# keyboard.net
KiCad netlist of a schematic drawn in EAGLE
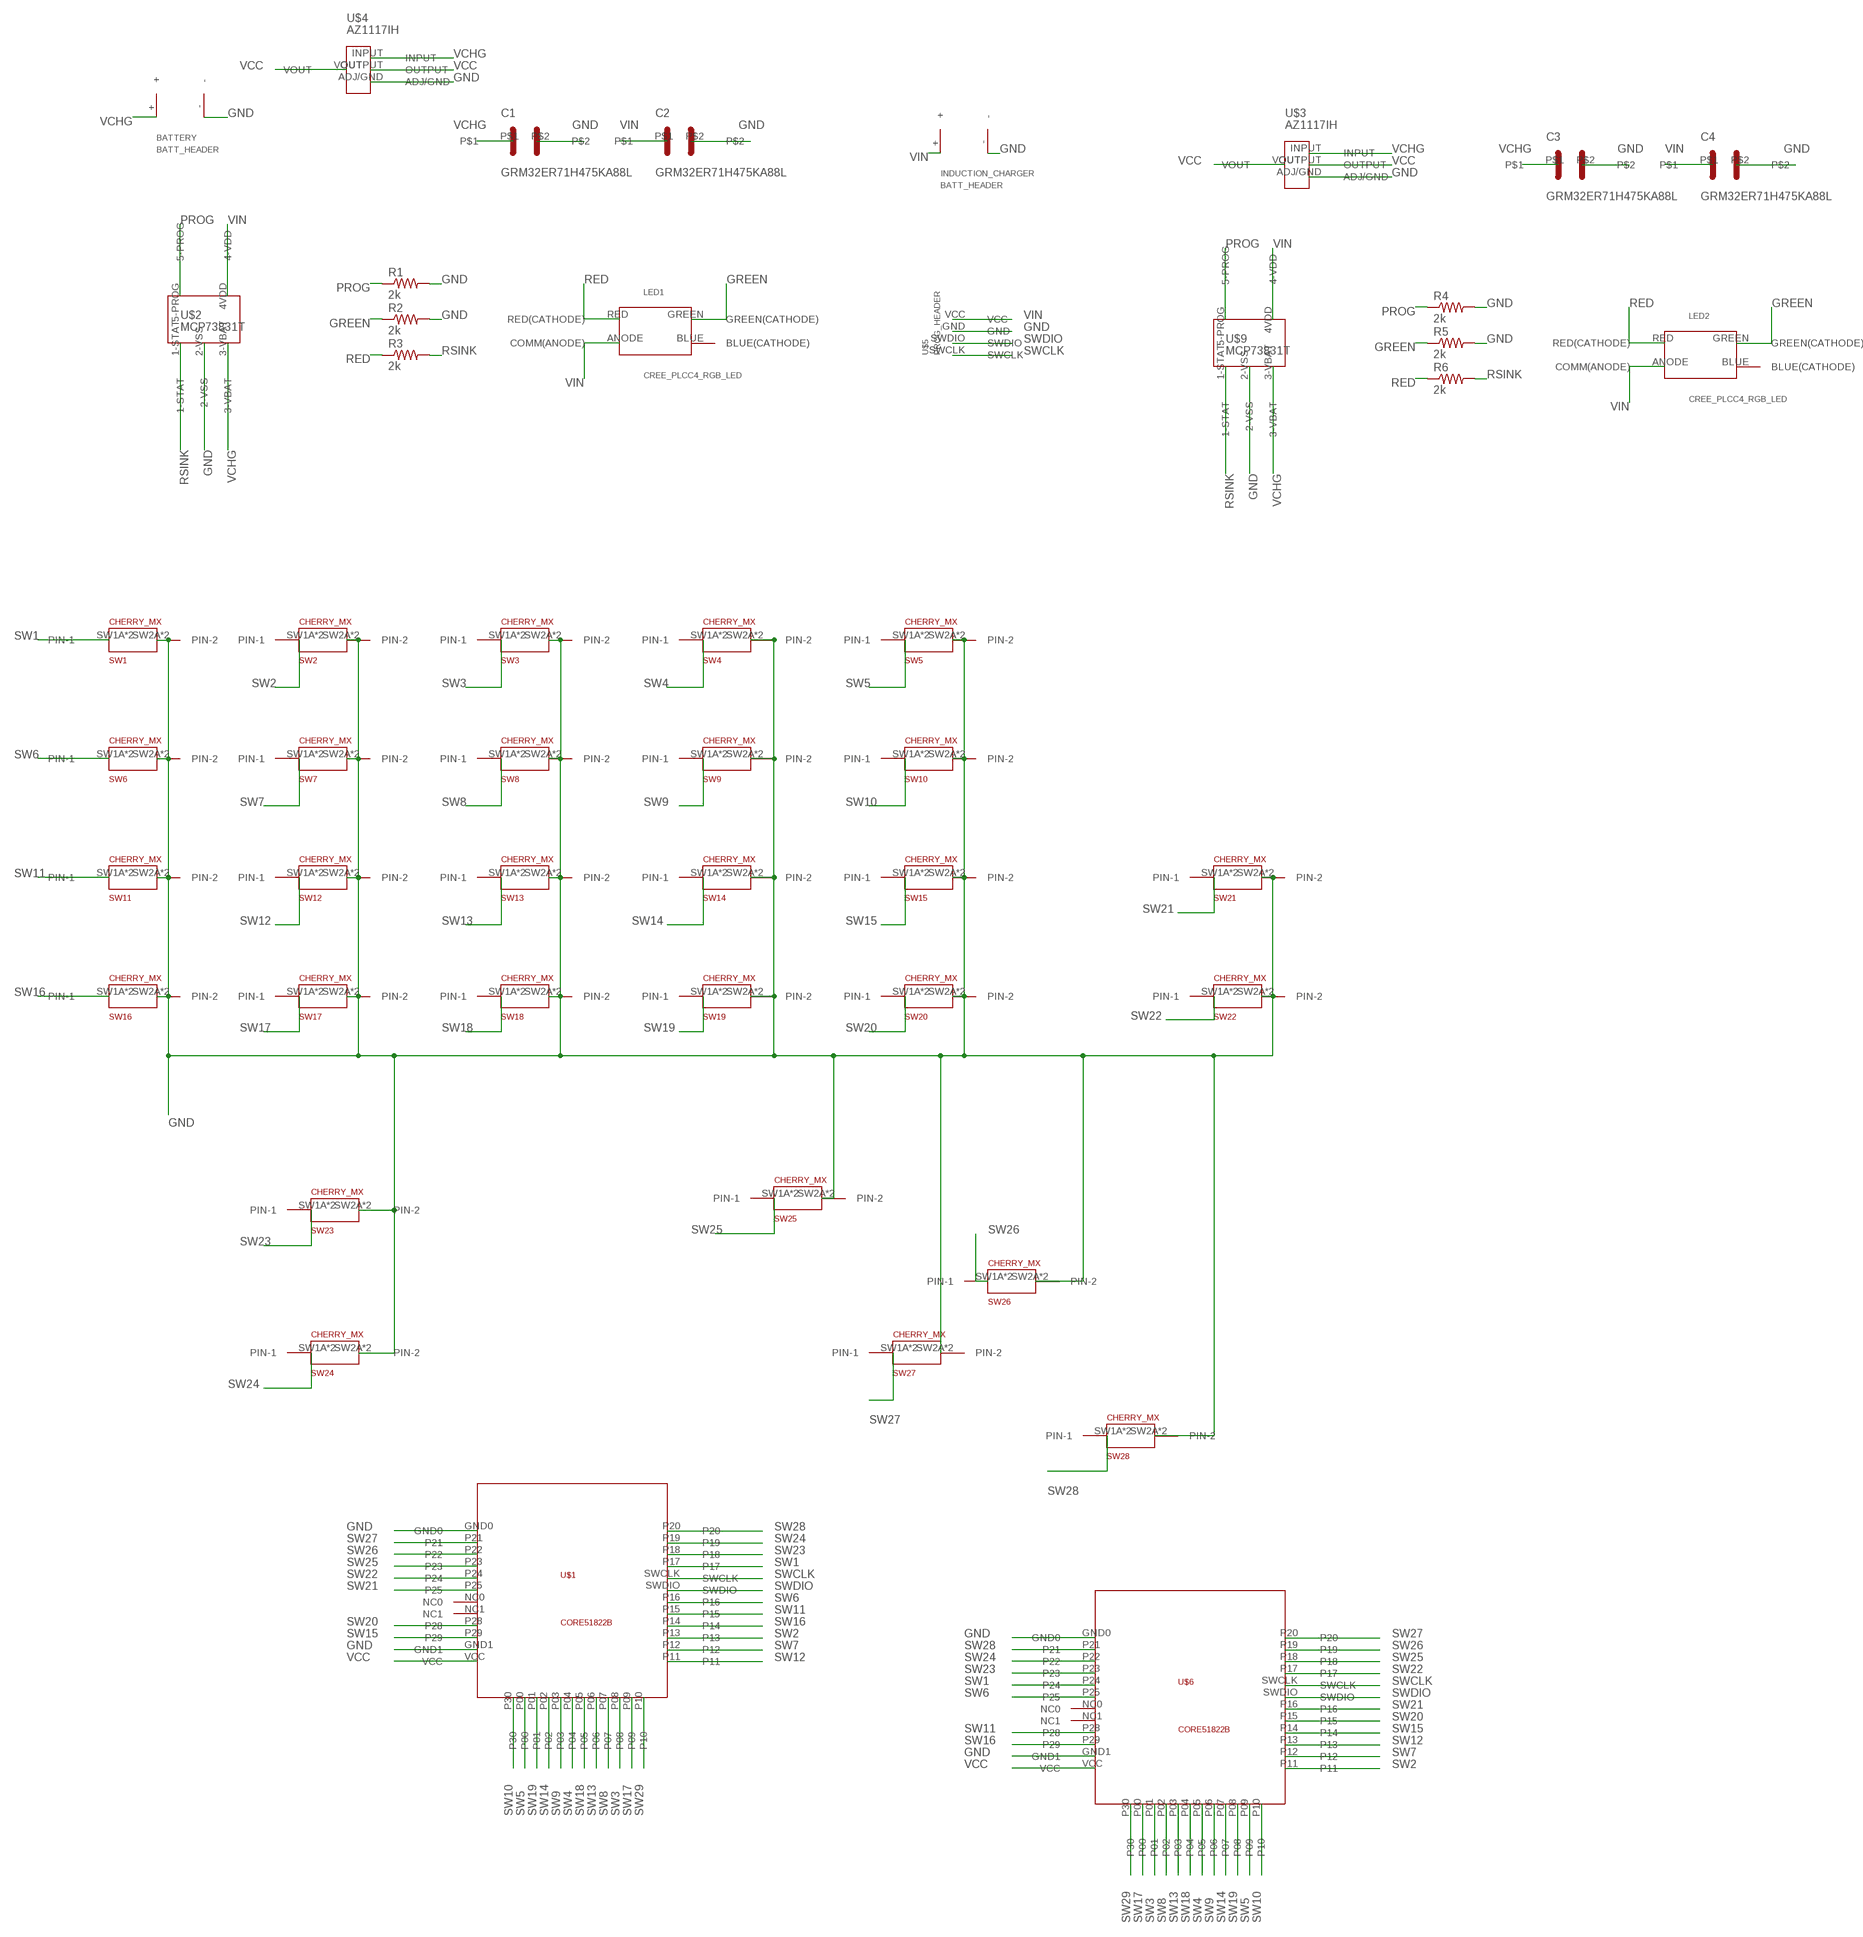
[diagram p0: schematic, sheet 1]

(export (version "E")
  (design (tool "Eeschema 10.0.6"))
  (components
    (comp (ref "BATTERY")
      (value "BATT_HEADER")
      (footprint "eagle-import:BATT_HEADER")
      (libsource (lib "eagle-import") (part "BATT_HEADER"))
    )
    (comp (ref "C1")
      (value "GRM32ER71H475KA88L")
      (footprint "eagle-import:GRM32ER71H475KA88L")
      (libsource (lib "eagle-import") (part "GRM32ER71H475KA88L"))
    )
    (comp (ref "C2")
      (value "GRM32ER71H475KA88L")
      (footprint "eagle-import:GRM32ER71H475KA88L")
      (libsource (lib "eagle-import") (part "GRM32ER71H475KA88L"))
    )
    (comp (ref "C3")
      (value "GRM32ER71H475KA88L")
      (footprint "eagle-import:GRM32ER71H475KA88L")
      (libsource (lib "eagle-import") (part "GRM32ER71H475KA88L"))
    )
    (comp (ref "C4")
      (value "GRM32ER71H475KA88L")
      (footprint "eagle-import:GRM32ER71H475KA88L")
      (libsource (lib "eagle-import") (part "GRM32ER71H475KA88L"))
    )
    (comp (ref "INDUCTION_CHARGER")
      (value "BATT_HEADER")
      (footprint "eagle-import:BATT_HEADER")
      (libsource (lib "eagle-import") (part "BATT_HEADER"))
    )
    (comp (ref "LED1")
      (value "CREE_PLCC4_RGB_LED")
      (footprint "eagle-import:4-PLCC")
      (libsource (lib "eagle-import") (part "CREE_PLCC4_RGB_LED"))
    )
    (comp (ref "LED2")
      (value "CREE_PLCC4_RGB_LED")
      (footprint "eagle-import:4-PLCC")
      (libsource (lib "eagle-import") (part "CREE_PLCC4_RGB_LED"))
    )
    (comp (ref "R1")
      (value "2k")
      (footprint "eagle-import:R1210")
      (libsource (lib "eagle-import") (part "R-US_R1210"))
    )
    (comp (ref "R2")
      (value "2k")
      (footprint "eagle-import:R1210")
      (libsource (lib "eagle-import") (part "R-US_R1210"))
    )
    (comp (ref "R3")
      (value "2k")
      (footprint "eagle-import:R1210")
      (libsource (lib "eagle-import") (part "R-US_R1210"))
    )
    (comp (ref "R4")
      (value "2k")
      (footprint "eagle-import:R1210")
      (libsource (lib "eagle-import") (part "R-US_R1210"))
    )
    (comp (ref "R5")
      (value "2k")
      (footprint "eagle-import:R1210")
      (libsource (lib "eagle-import") (part "R-US_R1210"))
    )
    (comp (ref "R6")
      (value "2k")
      (footprint "eagle-import:R1210")
      (libsource (lib "eagle-import") (part "R-US_R1210"))
    )
    (comp (ref "SW1")
      (value "CHERRY_MX")
      (footprint "eagle-import:CHERRY_MX")
      (libsource (lib "eagle-import") (part "CHERRY_MX"))
    )
    (comp (ref "SW2")
      (value "CHERRY_MX")
      (footprint "eagle-import:CHERRY_MX")
      (libsource (lib "eagle-import") (part "CHERRY_MX"))
    )
    (comp (ref "SW3")
      (value "CHERRY_MX")
      (footprint "eagle-import:CHERRY_MX")
      (libsource (lib "eagle-import") (part "CHERRY_MX"))
    )
    (comp (ref "SW4")
      (value "CHERRY_MX")
      (footprint "eagle-import:CHERRY_MX")
      (libsource (lib "eagle-import") (part "CHERRY_MX"))
    )
    (comp (ref "SW5")
      (value "CHERRY_MX")
      (footprint "eagle-import:CHERRY_MX")
      (libsource (lib "eagle-import") (part "CHERRY_MX"))
    )
    (comp (ref "SW6")
      (value "CHERRY_MX")
      (footprint "eagle-import:CHERRY_MX")
      (libsource (lib "eagle-import") (part "CHERRY_MX"))
    )
    (comp (ref "SW7")
      (value "CHERRY_MX")
      (footprint "eagle-import:CHERRY_MX")
      (libsource (lib "eagle-import") (part "CHERRY_MX"))
    )
    (comp (ref "SW8")
      (value "CHERRY_MX")
      (footprint "eagle-import:CHERRY_MX")
      (libsource (lib "eagle-import") (part "CHERRY_MX"))
    )
    (comp (ref "SW9")
      (value "CHERRY_MX")
      (footprint "eagle-import:CHERRY_MX")
      (libsource (lib "eagle-import") (part "CHERRY_MX"))
    )
    (comp (ref "SW10")
      (value "CHERRY_MX")
      (footprint "eagle-import:CHERRY_MX")
      (libsource (lib "eagle-import") (part "CHERRY_MX"))
    )
    (comp (ref "SW11")
      (value "CHERRY_MX")
      (footprint "eagle-import:CHERRY_MX")
      (libsource (lib "eagle-import") (part "CHERRY_MX"))
    )
    (comp (ref "SW12")
      (value "CHERRY_MX")
      (footprint "eagle-import:CHERRY_MX")
      (libsource (lib "eagle-import") (part "CHERRY_MX"))
    )
    (comp (ref "SW13")
      (value "CHERRY_MX")
      (footprint "eagle-import:CHERRY_MX")
      (libsource (lib "eagle-import") (part "CHERRY_MX"))
    )
    (comp (ref "SW14")
      (value "CHERRY_MX")
      (footprint "eagle-import:CHERRY_MX")
      (libsource (lib "eagle-import") (part "CHERRY_MX"))
    )
    (comp (ref "SW15")
      (value "CHERRY_MX")
      (footprint "eagle-import:CHERRY_MX")
      (libsource (lib "eagle-import") (part "CHERRY_MX"))
    )
    (comp (ref "SW16")
      (value "CHERRY_MX")
      (footprint "eagle-import:CHERRY_MX")
      (libsource (lib "eagle-import") (part "CHERRY_MX"))
    )
    (comp (ref "SW17")
      (value "CHERRY_MX")
      (footprint "eagle-import:CHERRY_MX")
      (libsource (lib "eagle-import") (part "CHERRY_MX"))
    )
    (comp (ref "SW18")
      (value "CHERRY_MX")
      (footprint "eagle-import:CHERRY_MX")
      (libsource (lib "eagle-import") (part "CHERRY_MX"))
    )
    (comp (ref "SW19")
      (value "CHERRY_MX")
      (footprint "eagle-import:CHERRY_MX")
      (libsource (lib "eagle-import") (part "CHERRY_MX"))
    )
    (comp (ref "SW20")
      (value "CHERRY_MX")
      (footprint "eagle-import:CHERRY_MX")
      (libsource (lib "eagle-import") (part "CHERRY_MX"))
    )
    (comp (ref "SW21")
      (value "CHERRY_MX")
      (footprint "eagle-import:CHERRY_MX")
      (libsource (lib "eagle-import") (part "CHERRY_MX"))
    )
    (comp (ref "SW22")
      (value "CHERRY_MX")
      (footprint "eagle-import:CHERRY_MX")
      (libsource (lib "eagle-import") (part "CHERRY_MX"))
    )
    (comp (ref "SW23")
      (value "CHERRY_MX")
      (footprint "eagle-import:CHERRY_MX")
      (libsource (lib "eagle-import") (part "CHERRY_MX"))
    )
    (comp (ref "SW24")
      (value "CHERRY_MX")
      (footprint "eagle-import:CHERRY_MX")
      (libsource (lib "eagle-import") (part "CHERRY_MX"))
    )
    (comp (ref "SW25")
      (value "CHERRY_MX")
      (footprint "eagle-import:CHERRY_MX")
      (libsource (lib "eagle-import") (part "CHERRY_MX"))
    )
    (comp (ref "SW26")
      (value "CHERRY_MX")
      (footprint "eagle-import:CHERRY_MX")
      (libsource (lib "eagle-import") (part "CHERRY_MX"))
    )
    (comp (ref "SW27")
      (value "CHERRY_MX")
      (footprint "eagle-import:CHERRY_MX")
      (libsource (lib "eagle-import") (part "CHERRY_MX"))
    )
    (comp (ref "SW28")
      (value "CHERRY_MX")
      (footprint "eagle-import:CHERRY_MX")
      (libsource (lib "eagle-import") (part "CHERRY_MX"))
    )
    (comp (ref "U$1")
      (value "CORE51822B")
      (footprint "eagle-import:CORE51822B")
      (libsource (lib "eagle-import") (part "CORE51822B"))
    )
    (comp (ref "U$2")
      (value "MCP73831T")
      (footprint "eagle-import:MCP73831T")
      (libsource (lib "eagle-import") (part "MCP73831T"))
    )
    (comp (ref "U$3")
      (value "AZ1117IH")
      (footprint "eagle-import:AZ1117IH")
      (libsource (lib "eagle-import") (part "AZ1117IH"))
    )
    (comp (ref "U$4")
      (value "AZ1117IH")
      (footprint "eagle-import:AZ1117IH")
      (libsource (lib "eagle-import") (part "AZ1117IH"))
    )
    (comp (ref "U$5")
      (value "PROG_HEADER")
      (footprint "eagle-import:PROG_HEADER")
      (libsource (lib "eagle-import") (part "PROG_HEADER"))
    )
    (comp (ref "U$6")
      (value "CORE51822B")
      (footprint "eagle-import:CORE51822B")
      (libsource (lib "eagle-import") (part "CORE51822B"))
    )
    (comp (ref "U$9")
      (value "MCP73831T")
      (footprint "eagle-import:MCP73831T")
      (libsource (lib "eagle-import") (part "MCP73831T"))
    )
  )
  (nets
    (net (code "1") (name "/GND") (class "Default")
      (node (ref "BATTERY") (pin "-") (pinfunction "-_-") (pintype "bidirectional"))
      (node (ref "C1") (pin "P$2") (pinfunction "P$2_P$2") (pintype "bidirectional"))
      (node (ref "C2") (pin "P$2") (pinfunction "P$2_P$2") (pintype "bidirectional"))
      (node (ref "C3") (pin "P$2") (pinfunction "P$2_P$2") (pintype "bidirectional"))
      (node (ref "C4") (pin "P$2") (pinfunction "P$2_P$2") (pintype "bidirectional"))
      (node (ref "INDUCTION_CHARGER") (pin "-") (pinfunction "-_-") (pintype "bidirectional"))
      (node (ref "R1") (pin "2") (pinfunction "2_2") (pintype "passive"))
      (node (ref "R2") (pin "2") (pinfunction "2_2") (pintype "passive"))
      (node (ref "R4") (pin "2") (pinfunction "2_2") (pintype "passive"))
      (node (ref "R5") (pin "2") (pinfunction "2_2") (pintype "passive"))
      (node (ref "SW1") (pin "SW2A") (pinfunction "PIN-2_SW2A") (pintype "bidirectional"))
      (node (ref "SW1") (pin "SW2B") (pinfunction "PIN-2_SW2B") (pintype "bidirectional"))
      (node (ref "SW10") (pin "SW2A") (pinfunction "PIN-2_SW2A") (pintype "bidirectional"))
      (node (ref "SW10") (pin "SW2B") (pinfunction "PIN-2_SW2B") (pintype "bidirectional"))
      (node (ref "SW11") (pin "SW2A") (pinfunction "PIN-2_SW2A") (pintype "bidirectional"))
      (node (ref "SW11") (pin "SW2B") (pinfunction "PIN-2_SW2B") (pintype "bidirectional"))
      (node (ref "SW12") (pin "SW2A") (pinfunction "PIN-2_SW2A") (pintype "bidirectional"))
      (node (ref "SW12") (pin "SW2B") (pinfunction "PIN-2_SW2B") (pintype "bidirectional"))
      (node (ref "SW13") (pin "SW2A") (pinfunction "PIN-2_SW2A") (pintype "bidirectional"))
      (node (ref "SW13") (pin "SW2B") (pinfunction "PIN-2_SW2B") (pintype "bidirectional"))
      (node (ref "SW14") (pin "SW2A") (pinfunction "PIN-2_SW2A") (pintype "bidirectional"))
      (node (ref "SW14") (pin "SW2B") (pinfunction "PIN-2_SW2B") (pintype "bidirectional"))
      (node (ref "SW15") (pin "SW2A") (pinfunction "PIN-2_SW2A") (pintype "bidirectional"))
      (node (ref "SW15") (pin "SW2B") (pinfunction "PIN-2_SW2B") (pintype "bidirectional"))
      (node (ref "SW16") (pin "SW2A") (pinfunction "PIN-2_SW2A") (pintype "bidirectional"))
      (node (ref "SW16") (pin "SW2B") (pinfunction "PIN-2_SW2B") (pintype "bidirectional"))
      (node (ref "SW17") (pin "SW2A") (pinfunction "PIN-2_SW2A") (pintype "bidirectional"))
      (node (ref "SW17") (pin "SW2B") (pinfunction "PIN-2_SW2B") (pintype "bidirectional"))
      (node (ref "SW18") (pin "SW2A") (pinfunction "PIN-2_SW2A") (pintype "bidirectional"))
      (node (ref "SW18") (pin "SW2B") (pinfunction "PIN-2_SW2B") (pintype "bidirectional"))
      (node (ref "SW19") (pin "SW2A") (pinfunction "PIN-2_SW2A") (pintype "bidirectional"))
      (node (ref "SW19") (pin "SW2B") (pinfunction "PIN-2_SW2B") (pintype "bidirectional"))
      (node (ref "SW2") (pin "SW2A") (pinfunction "PIN-2_SW2A") (pintype "bidirectional"))
      (node (ref "SW2") (pin "SW2B") (pinfunction "PIN-2_SW2B") (pintype "bidirectional"))
      (node (ref "SW20") (pin "SW2A") (pinfunction "PIN-2_SW2A") (pintype "bidirectional"))
      (node (ref "SW20") (pin "SW2B") (pinfunction "PIN-2_SW2B") (pintype "bidirectional"))
      (node (ref "SW21") (pin "SW2A") (pinfunction "PIN-2_SW2A") (pintype "bidirectional"))
      (node (ref "SW21") (pin "SW2B") (pinfunction "PIN-2_SW2B") (pintype "bidirectional"))
      (node (ref "SW22") (pin "SW2A") (pinfunction "PIN-2_SW2A") (pintype "bidirectional"))
      (node (ref "SW22") (pin "SW2B") (pinfunction "PIN-2_SW2B") (pintype "bidirectional"))
      (node (ref "SW23") (pin "SW2A") (pinfunction "PIN-2_SW2A") (pintype "bidirectional"))
      (node (ref "SW23") (pin "SW2B") (pinfunction "PIN-2_SW2B") (pintype "bidirectional"))
      (node (ref "SW24") (pin "SW2A") (pinfunction "PIN-2_SW2A") (pintype "bidirectional"))
      (node (ref "SW24") (pin "SW2B") (pinfunction "PIN-2_SW2B") (pintype "bidirectional"))
      (node (ref "SW25") (pin "SW2A") (pinfunction "PIN-2_SW2A") (pintype "bidirectional"))
      (node (ref "SW25") (pin "SW2B") (pinfunction "PIN-2_SW2B") (pintype "bidirectional"))
      (node (ref "SW26") (pin "SW2A") (pinfunction "PIN-2_SW2A") (pintype "bidirectional"))
      (node (ref "SW26") (pin "SW2B") (pinfunction "PIN-2_SW2B") (pintype "bidirectional"))
      (node (ref "SW27") (pin "SW2A") (pinfunction "PIN-2_SW2A") (pintype "bidirectional"))
      (node (ref "SW27") (pin "SW2B") (pinfunction "PIN-2_SW2B") (pintype "bidirectional"))
      (node (ref "SW28") (pin "SW2A") (pinfunction "PIN-2_SW2A") (pintype "bidirectional"))
      (node (ref "SW28") (pin "SW2B") (pinfunction "PIN-2_SW2B") (pintype "bidirectional"))
      (node (ref "SW3") (pin "SW2A") (pinfunction "PIN-2_SW2A") (pintype "bidirectional"))
      (node (ref "SW3") (pin "SW2B") (pinfunction "PIN-2_SW2B") (pintype "bidirectional"))
      (node (ref "SW4") (pin "SW2A") (pinfunction "PIN-2_SW2A") (pintype "bidirectional"))
      (node (ref "SW4") (pin "SW2B") (pinfunction "PIN-2_SW2B") (pintype "bidirectional"))
      (node (ref "SW5") (pin "SW2A") (pinfunction "PIN-2_SW2A") (pintype "bidirectional"))
      (node (ref "SW5") (pin "SW2B") (pinfunction "PIN-2_SW2B") (pintype "bidirectional"))
      (node (ref "SW6") (pin "SW2A") (pinfunction "PIN-2_SW2A") (pintype "bidirectional"))
      (node (ref "SW6") (pin "SW2B") (pinfunction "PIN-2_SW2B") (pintype "bidirectional"))
      (node (ref "SW7") (pin "SW2A") (pinfunction "PIN-2_SW2A") (pintype "bidirectional"))
      (node (ref "SW7") (pin "SW2B") (pinfunction "PIN-2_SW2B") (pintype "bidirectional"))
      (node (ref "SW8") (pin "SW2A") (pinfunction "PIN-2_SW2A") (pintype "bidirectional"))
      (node (ref "SW8") (pin "SW2B") (pinfunction "PIN-2_SW2B") (pintype "bidirectional"))
      (node (ref "SW9") (pin "SW2A") (pinfunction "PIN-2_SW2A") (pintype "bidirectional"))
      (node (ref "SW9") (pin "SW2B") (pinfunction "PIN-2_SW2B") (pintype "bidirectional"))
      (node (ref "U$1") (pin "GND0") (pinfunction "GND0_GND0") (pintype "bidirectional"))
      (node (ref "U$1") (pin "GND1") (pinfunction "GND1_GND1") (pintype "bidirectional"))
      (node (ref "U$2") (pin "2-VSS") (pinfunction "2-VSS_2-VSS") (pintype "bidirectional"))
      (node (ref "U$3") (pin "ADJ/GND") (pinfunction "ADJ/GND_ADJ/GND") (pintype "bidirectional"))
      (node (ref "U$4") (pin "ADJ/GND") (pinfunction "ADJ/GND_ADJ/GND") (pintype "bidirectional"))
      (node (ref "U$5") (pin "GND") (pinfunction "GND_GND") (pintype "bidirectional"))
      (node (ref "U$6") (pin "GND0") (pinfunction "GND0_GND0") (pintype "bidirectional"))
      (node (ref "U$6") (pin "GND1") (pinfunction "GND1_GND1") (pintype "bidirectional"))
      (node (ref "U$9") (pin "2-VSS") (pinfunction "2-VSS_2-VSS") (pintype "bidirectional"))
    )
    (net (code "2") (name "/GREEN") (class "Default")
      (node (ref "LED1") (pin "GREEN") (pinfunction "GREEN(CATHODE)_GREEN") (pintype "bidirectional"))
      (node (ref "LED2") (pin "GREEN") (pinfunction "GREEN(CATHODE)_GREEN") (pintype "bidirectional"))
      (node (ref "R2") (pin "1") (pinfunction "1_1") (pintype "passive"))
      (node (ref "R5") (pin "1") (pinfunction "1_1") (pintype "passive"))
    )
    (net (code "3") (name "/PROG") (class "Default")
      (node (ref "R1") (pin "1") (pinfunction "1_1") (pintype "passive"))
      (node (ref "R4") (pin "1") (pinfunction "1_1") (pintype "passive"))
      (node (ref "U$2") (pin "5-PROG") (pinfunction "5-PROG_5-PROG") (pintype "bidirectional"))
      (node (ref "U$9") (pin "5-PROG") (pinfunction "5-PROG_5-PROG") (pintype "bidirectional"))
    )
    (net (code "4") (name "/RED") (class "Default")
      (node (ref "LED1") (pin "RED") (pinfunction "RED(CATHODE)_RED") (pintype "bidirectional"))
      (node (ref "LED2") (pin "RED") (pinfunction "RED(CATHODE)_RED") (pintype "bidirectional"))
      (node (ref "R3") (pin "1") (pinfunction "1_1") (pintype "passive"))
      (node (ref "R6") (pin "1") (pinfunction "1_1") (pintype "passive"))
    )
    (net (code "5") (name "/RSINK") (class "Default")
      (node (ref "R3") (pin "2") (pinfunction "2_2") (pintype "passive"))
      (node (ref "R6") (pin "2") (pinfunction "2_2") (pintype "passive"))
      (node (ref "U$2") (pin "1-STAT") (pinfunction "1-STAT_1-STAT") (pintype "bidirectional"))
      (node (ref "U$9") (pin "1-STAT") (pinfunction "1-STAT_1-STAT") (pintype "bidirectional"))
    )
    (net (code "6") (name "/SW1") (class "Default")
      (node (ref "SW1") (pin "SW1A") (pinfunction "PIN-1_SW1A") (pintype "bidirectional"))
      (node (ref "SW1") (pin "SW1B") (pinfunction "PIN-1_SW1B") (pintype "bidirectional"))
      (node (ref "U$1") (pin "P17") (pinfunction "P17_P17") (pintype "bidirectional"))
      (node (ref "U$6") (pin "P24") (pinfunction "P24_P24") (pintype "bidirectional"))
    )
    (net (code "7") (name "/SW2") (class "Default")
      (node (ref "SW2") (pin "SW1A") (pinfunction "PIN-1_SW1A") (pintype "bidirectional"))
      (node (ref "SW2") (pin "SW1B") (pinfunction "PIN-1_SW1B") (pintype "bidirectional"))
      (node (ref "U$1") (pin "P13") (pinfunction "P13_P13") (pintype "bidirectional"))
      (node (ref "U$6") (pin "P11") (pinfunction "P11_P11") (pintype "bidirectional"))
    )
    (net (code "8") (name "/SW3") (class "Default")
      (node (ref "SW3") (pin "SW1A") (pinfunction "PIN-1_SW1A") (pintype "bidirectional"))
      (node (ref "SW3") (pin "SW1B") (pinfunction "PIN-1_SW1B") (pintype "bidirectional"))
      (node (ref "U$1") (pin "P08") (pinfunction "P08_P08") (pintype "bidirectional"))
      (node (ref "U$6") (pin "P01") (pinfunction "P01_P01") (pintype "bidirectional"))
    )
    (net (code "9") (name "/SW4") (class "Default")
      (node (ref "SW4") (pin "SW1A") (pinfunction "PIN-1_SW1A") (pintype "bidirectional"))
      (node (ref "SW4") (pin "SW1B") (pinfunction "PIN-1_SW1B") (pintype "bidirectional"))
      (node (ref "U$1") (pin "P04") (pinfunction "P04_P04") (pintype "bidirectional"))
      (node (ref "U$6") (pin "P05") (pinfunction "P05_P05") (pintype "bidirectional"))
    )
    (net (code "10") (name "/SW5") (class "Default")
      (node (ref "SW5") (pin "SW1A") (pinfunction "PIN-1_SW1A") (pintype "bidirectional"))
      (node (ref "SW5") (pin "SW1B") (pinfunction "PIN-1_SW1B") (pintype "bidirectional"))
      (node (ref "U$1") (pin "P00") (pinfunction "P00_P00") (pintype "bidirectional"))
      (node (ref "U$6") (pin "P09") (pinfunction "P09_P09") (pintype "bidirectional"))
    )
    (net (code "11") (name "/SW6") (class "Default")
      (node (ref "SW6") (pin "SW1A") (pinfunction "PIN-1_SW1A") (pintype "bidirectional"))
      (node (ref "SW6") (pin "SW1B") (pinfunction "PIN-1_SW1B") (pintype "bidirectional"))
      (node (ref "U$1") (pin "P16") (pinfunction "P16_P16") (pintype "bidirectional"))
      (node (ref "U$6") (pin "P25") (pinfunction "P25_P25") (pintype "bidirectional"))
    )
    (net (code "12") (name "/SW7") (class "Default")
      (node (ref "SW7") (pin "SW1A") (pinfunction "PIN-1_SW1A") (pintype "bidirectional"))
      (node (ref "SW7") (pin "SW1B") (pinfunction "PIN-1_SW1B") (pintype "bidirectional"))
      (node (ref "U$1") (pin "P12") (pinfunction "P12_P12") (pintype "bidirectional"))
      (node (ref "U$6") (pin "P12") (pinfunction "P12_P12") (pintype "bidirectional"))
    )
    (net (code "13") (name "/SW8") (class "Default")
      (node (ref "SW8") (pin "SW1A") (pinfunction "PIN-1_SW1A") (pintype "bidirectional"))
      (node (ref "SW8") (pin "SW1B") (pinfunction "PIN-1_SW1B") (pintype "bidirectional"))
      (node (ref "U$1") (pin "P07") (pinfunction "P07_P07") (pintype "bidirectional"))
      (node (ref "U$6") (pin "P02") (pinfunction "P02_P02") (pintype "bidirectional"))
    )
    (net (code "14") (name "/SW9") (class "Default")
      (node (ref "SW9") (pin "SW1A") (pinfunction "PIN-1_SW1A") (pintype "bidirectional"))
      (node (ref "SW9") (pin "SW1B") (pinfunction "PIN-1_SW1B") (pintype "bidirectional"))
      (node (ref "U$1") (pin "P03") (pinfunction "P03_P03") (pintype "bidirectional"))
      (node (ref "U$6") (pin "P06") (pinfunction "P06_P06") (pintype "bidirectional"))
    )
    (net (code "15") (name "/SW10") (class "Default")
      (node (ref "SW10") (pin "SW1A") (pinfunction "PIN-1_SW1A") (pintype "bidirectional"))
      (node (ref "SW10") (pin "SW1B") (pinfunction "PIN-1_SW1B") (pintype "bidirectional"))
      (node (ref "U$1") (pin "P30") (pinfunction "P30_P30") (pintype "bidirectional"))
      (node (ref "U$6") (pin "P10") (pinfunction "P10_P10") (pintype "bidirectional"))
    )
    (net (code "16") (name "/SW11") (class "Default")
      (node (ref "SW11") (pin "SW1A") (pinfunction "PIN-1_SW1A") (pintype "bidirectional"))
      (node (ref "SW11") (pin "SW1B") (pinfunction "PIN-1_SW1B") (pintype "bidirectional"))
      (node (ref "U$1") (pin "P15") (pinfunction "P15_P15") (pintype "bidirectional"))
      (node (ref "U$6") (pin "P28") (pinfunction "P28_P28") (pintype "bidirectional"))
    )
    (net (code "17") (name "/SW12") (class "Default")
      (node (ref "SW12") (pin "SW1A") (pinfunction "PIN-1_SW1A") (pintype "bidirectional"))
      (node (ref "SW12") (pin "SW1B") (pinfunction "PIN-1_SW1B") (pintype "bidirectional"))
      (node (ref "U$1") (pin "P11") (pinfunction "P11_P11") (pintype "bidirectional"))
      (node (ref "U$6") (pin "P13") (pinfunction "P13_P13") (pintype "bidirectional"))
    )
    (net (code "18") (name "/SW13") (class "Default")
      (node (ref "SW13") (pin "SW1A") (pinfunction "PIN-1_SW1A") (pintype "bidirectional"))
      (node (ref "SW13") (pin "SW1B") (pinfunction "PIN-1_SW1B") (pintype "bidirectional"))
      (node (ref "U$1") (pin "P06") (pinfunction "P06_P06") (pintype "bidirectional"))
      (node (ref "U$6") (pin "P03") (pinfunction "P03_P03") (pintype "bidirectional"))
    )
    (net (code "19") (name "/SW14") (class "Default")
      (node (ref "SW14") (pin "SW1A") (pinfunction "PIN-1_SW1A") (pintype "bidirectional"))
      (node (ref "SW14") (pin "SW1B") (pinfunction "PIN-1_SW1B") (pintype "bidirectional"))
      (node (ref "U$1") (pin "P02") (pinfunction "P02_P02") (pintype "bidirectional"))
      (node (ref "U$6") (pin "P07") (pinfunction "P07_P07") (pintype "bidirectional"))
    )
    (net (code "20") (name "/SW15") (class "Default")
      (node (ref "SW15") (pin "SW1A") (pinfunction "PIN-1_SW1A") (pintype "bidirectional"))
      (node (ref "SW15") (pin "SW1B") (pinfunction "PIN-1_SW1B") (pintype "bidirectional"))
      (node (ref "U$1") (pin "P29") (pinfunction "P29_P29") (pintype "bidirectional"))
      (node (ref "U$6") (pin "P14") (pinfunction "P14_P14") (pintype "bidirectional"))
    )
    (net (code "21") (name "/SW16") (class "Default")
      (node (ref "SW16") (pin "SW1A") (pinfunction "PIN-1_SW1A") (pintype "bidirectional"))
      (node (ref "SW16") (pin "SW1B") (pinfunction "PIN-1_SW1B") (pintype "bidirectional"))
      (node (ref "U$1") (pin "P14") (pinfunction "P14_P14") (pintype "bidirectional"))
      (node (ref "U$6") (pin "P29") (pinfunction "P29_P29") (pintype "bidirectional"))
    )
    (net (code "22") (name "/SW17") (class "Default")
      (node (ref "SW17") (pin "SW1A") (pinfunction "PIN-1_SW1A") (pintype "bidirectional"))
      (node (ref "SW17") (pin "SW1B") (pinfunction "PIN-1_SW1B") (pintype "bidirectional"))
      (node (ref "U$1") (pin "P09") (pinfunction "P09_P09") (pintype "bidirectional"))
      (node (ref "U$6") (pin "P00") (pinfunction "P00_P00") (pintype "bidirectional"))
    )
    (net (code "23") (name "/SW18") (class "Default")
      (node (ref "SW18") (pin "SW1A") (pinfunction "PIN-1_SW1A") (pintype "bidirectional"))
      (node (ref "SW18") (pin "SW1B") (pinfunction "PIN-1_SW1B") (pintype "bidirectional"))
      (node (ref "U$1") (pin "P05") (pinfunction "P05_P05") (pintype "bidirectional"))
      (node (ref "U$6") (pin "P04") (pinfunction "P04_P04") (pintype "bidirectional"))
    )
    (net (code "24") (name "/SW19") (class "Default")
      (node (ref "SW19") (pin "SW1A") (pinfunction "PIN-1_SW1A") (pintype "bidirectional"))
      (node (ref "SW19") (pin "SW1B") (pinfunction "PIN-1_SW1B") (pintype "bidirectional"))
      (node (ref "U$1") (pin "P01") (pinfunction "P01_P01") (pintype "bidirectional"))
      (node (ref "U$6") (pin "P08") (pinfunction "P08_P08") (pintype "bidirectional"))
    )
    (net (code "25") (name "/SW20") (class "Default")
      (node (ref "SW20") (pin "SW1A") (pinfunction "PIN-1_SW1A") (pintype "bidirectional"))
      (node (ref "SW20") (pin "SW1B") (pinfunction "PIN-1_SW1B") (pintype "bidirectional"))
      (node (ref "U$1") (pin "P28") (pinfunction "P28_P28") (pintype "bidirectional"))
      (node (ref "U$6") (pin "P15") (pinfunction "P15_P15") (pintype "bidirectional"))
    )
    (net (code "26") (name "/SW21") (class "Default")
      (node (ref "SW21") (pin "SW1A") (pinfunction "PIN-1_SW1A") (pintype "bidirectional"))
      (node (ref "SW21") (pin "SW1B") (pinfunction "PIN-1_SW1B") (pintype "bidirectional"))
      (node (ref "U$1") (pin "P25") (pinfunction "P25_P25") (pintype "bidirectional"))
      (node (ref "U$6") (pin "P16") (pinfunction "P16_P16") (pintype "bidirectional"))
    )
    (net (code "27") (name "/SW22") (class "Default")
      (node (ref "SW22") (pin "SW1A") (pinfunction "PIN-1_SW1A") (pintype "bidirectional"))
      (node (ref "SW22") (pin "SW1B") (pinfunction "PIN-1_SW1B") (pintype "bidirectional"))
      (node (ref "U$1") (pin "P24") (pinfunction "P24_P24") (pintype "bidirectional"))
      (node (ref "U$6") (pin "P17") (pinfunction "P17_P17") (pintype "bidirectional"))
    )
    (net (code "28") (name "/SW23") (class "Default")
      (node (ref "SW23") (pin "SW1A") (pinfunction "PIN-1_SW1A") (pintype "bidirectional"))
      (node (ref "SW23") (pin "SW1B") (pinfunction "PIN-1_SW1B") (pintype "bidirectional"))
      (node (ref "U$1") (pin "P18") (pinfunction "P18_P18") (pintype "bidirectional"))
      (node (ref "U$6") (pin "P23") (pinfunction "P23_P23") (pintype "bidirectional"))
    )
    (net (code "29") (name "/SW24") (class "Default")
      (node (ref "SW24") (pin "SW1A") (pinfunction "PIN-1_SW1A") (pintype "bidirectional"))
      (node (ref "SW24") (pin "SW1B") (pinfunction "PIN-1_SW1B") (pintype "bidirectional"))
      (node (ref "U$1") (pin "P19") (pinfunction "P19_P19") (pintype "bidirectional"))
      (node (ref "U$6") (pin "P22") (pinfunction "P22_P22") (pintype "bidirectional"))
    )
    (net (code "30") (name "/SW25") (class "Default")
      (node (ref "SW25") (pin "SW1A") (pinfunction "PIN-1_SW1A") (pintype "bidirectional"))
      (node (ref "SW25") (pin "SW1B") (pinfunction "PIN-1_SW1B") (pintype "bidirectional"))
      (node (ref "U$1") (pin "P23") (pinfunction "P23_P23") (pintype "bidirectional"))
      (node (ref "U$6") (pin "P18") (pinfunction "P18_P18") (pintype "bidirectional"))
    )
    (net (code "31") (name "/SW26") (class "Default")
      (node (ref "SW26") (pin "SW1A") (pinfunction "PIN-1_SW1A") (pintype "bidirectional"))
      (node (ref "SW26") (pin "SW1B") (pinfunction "PIN-1_SW1B") (pintype "bidirectional"))
      (node (ref "U$1") (pin "P22") (pinfunction "P22_P22") (pintype "bidirectional"))
      (node (ref "U$6") (pin "P19") (pinfunction "P19_P19") (pintype "bidirectional"))
    )
    (net (code "32") (name "/SW27") (class "Default")
      (node (ref "SW27") (pin "SW1A") (pinfunction "PIN-1_SW1A") (pintype "bidirectional"))
      (node (ref "SW27") (pin "SW1B") (pinfunction "PIN-1_SW1B") (pintype "bidirectional"))
      (node (ref "U$1") (pin "P21") (pinfunction "P21_P21") (pintype "bidirectional"))
      (node (ref "U$6") (pin "P20") (pinfunction "P20_P20") (pintype "bidirectional"))
    )
    (net (code "33") (name "/SW28") (class "Default")
      (node (ref "SW28") (pin "SW1A") (pinfunction "PIN-1_SW1A") (pintype "bidirectional"))
      (node (ref "SW28") (pin "SW1B") (pinfunction "PIN-1_SW1B") (pintype "bidirectional"))
      (node (ref "U$1") (pin "P20") (pinfunction "P20_P20") (pintype "bidirectional"))
      (node (ref "U$6") (pin "P21") (pinfunction "P21_P21") (pintype "bidirectional"))
    )
    (net (code "34") (name "/SW29") (class "Default")
      (node (ref "U$1") (pin "P10") (pinfunction "P10_P10") (pintype "bidirectional"))
      (node (ref "U$6") (pin "P30") (pinfunction "P30_P30") (pintype "bidirectional"))
    )
    (net (code "35") (name "/SWCLK") (class "Default")
      (node (ref "U$1") (pin "SWCLK") (pinfunction "SWCLK_SWCLK") (pintype "bidirectional"))
      (node (ref "U$5") (pin "SWCLK") (pinfunction "SWCLK_SWCLK") (pintype "bidirectional"))
      (node (ref "U$6") (pin "SWCLK") (pinfunction "SWCLK_SWCLK") (pintype "bidirectional"))
    )
    (net (code "36") (name "/SWDIO") (class "Default")
      (node (ref "U$1") (pin "SWDIO") (pinfunction "SWDIO_SWDIO") (pintype "bidirectional"))
      (node (ref "U$5") (pin "SWDIO") (pinfunction "SWDIO_SWDIO") (pintype "bidirectional"))
      (node (ref "U$6") (pin "SWDIO") (pinfunction "SWDIO_SWDIO") (pintype "bidirectional"))
    )
    (net (code "37") (name "/VCC") (class "Default")
      (node (ref "U$1") (pin "VCC") (pinfunction "VCC_VCC") (pintype "bidirectional"))
      (node (ref "U$3") (pin "OUTPUT") (pinfunction "OUTPUT_OUTPUT") (pintype "bidirectional"))
      (node (ref "U$3") (pin "VOUT") (pinfunction "VOUT_VOUT") (pintype "bidirectional"))
      (node (ref "U$4") (pin "OUTPUT") (pinfunction "OUTPUT_OUTPUT") (pintype "bidirectional"))
      (node (ref "U$4") (pin "VOUT") (pinfunction "VOUT_VOUT") (pintype "bidirectional"))
      (node (ref "U$6") (pin "VCC") (pinfunction "VCC_VCC") (pintype "bidirectional"))
    )
    (net (code "38") (name "/VCHG") (class "Default")
      (node (ref "BATTERY") (pin "+") (pinfunction "+_+") (pintype "bidirectional"))
      (node (ref "C1") (pin "P$1") (pinfunction "P$1_P$1") (pintype "bidirectional"))
      (node (ref "C3") (pin "P$1") (pinfunction "P$1_P$1") (pintype "bidirectional"))
      (node (ref "U$2") (pin "3-VBAT") (pinfunction "3-VBAT_3-VBAT") (pintype "bidirectional"))
      (node (ref "U$3") (pin "INPUT") (pinfunction "INPUT_INPUT") (pintype "bidirectional"))
      (node (ref "U$4") (pin "INPUT") (pinfunction "INPUT_INPUT") (pintype "bidirectional"))
      (node (ref "U$9") (pin "3-VBAT") (pinfunction "3-VBAT_3-VBAT") (pintype "bidirectional"))
    )
    (net (code "39") (name "/VIN") (class "Default")
      (node (ref "C2") (pin "P$1") (pinfunction "P$1_P$1") (pintype "bidirectional"))
      (node (ref "C4") (pin "P$1") (pinfunction "P$1_P$1") (pintype "bidirectional"))
      (node (ref "INDUCTION_CHARGER") (pin "+") (pinfunction "+_+") (pintype "bidirectional"))
      (node (ref "LED1") (pin "ANODE") (pinfunction "COMM(ANODE)_ANODE") (pintype "bidirectional"))
      (node (ref "LED2") (pin "ANODE") (pinfunction "COMM(ANODE)_ANODE") (pintype "bidirectional"))
      (node (ref "U$2") (pin "4VDD") (pinfunction "4-VDD_4VDD") (pintype "bidirectional"))
      (node (ref "U$5") (pin "VCC") (pinfunction "VCC_VCC") (pintype "bidirectional"))
      (node (ref "U$9") (pin "4VDD") (pinfunction "4-VDD_4VDD") (pintype "bidirectional"))
    )
    (net (code "40") (name "unconnected-(LED1-BLUE(CATHODE)-PadBLUE)") (class "Default")
      (node (ref "LED1") (pin "BLUE") (pinfunction "BLUE(CATHODE)_BLUE") (pintype "bidirectional"))
    )
    (net (code "41") (name "unconnected-(LED2-BLUE(CATHODE)-PadBLUE)") (class "Default")
      (node (ref "LED2") (pin "BLUE") (pinfunction "BLUE(CATHODE)_BLUE") (pintype "bidirectional"))
    )
    (net (code "42") (name "unconnected-(U$1-PadNC0)") (class "Default")
      (node (ref "U$1") (pin "NC0") (pinfunction "NC0_NC0") (pintype "bidirectional"))
    )
    (net (code "43") (name "unconnected-(U$1-PadNC1)") (class "Default")
      (node (ref "U$1") (pin "NC1") (pinfunction "NC1_NC1") (pintype "bidirectional"))
    )
    (net (code "44") (name "unconnected-(U$6-PadNC0)") (class "Default")
      (node (ref "U$6") (pin "NC0") (pinfunction "NC0_NC0") (pintype "bidirectional"))
    )
    (net (code "45") (name "unconnected-(U$6-PadNC1)") (class "Default")
      (node (ref "U$6") (pin "NC1") (pinfunction "NC1_NC1") (pintype "bidirectional"))
    )
  )
)
